# Puzzle_OLED128x32-I2C.net
KiCad netlist of a schematic drawn in EAGLE
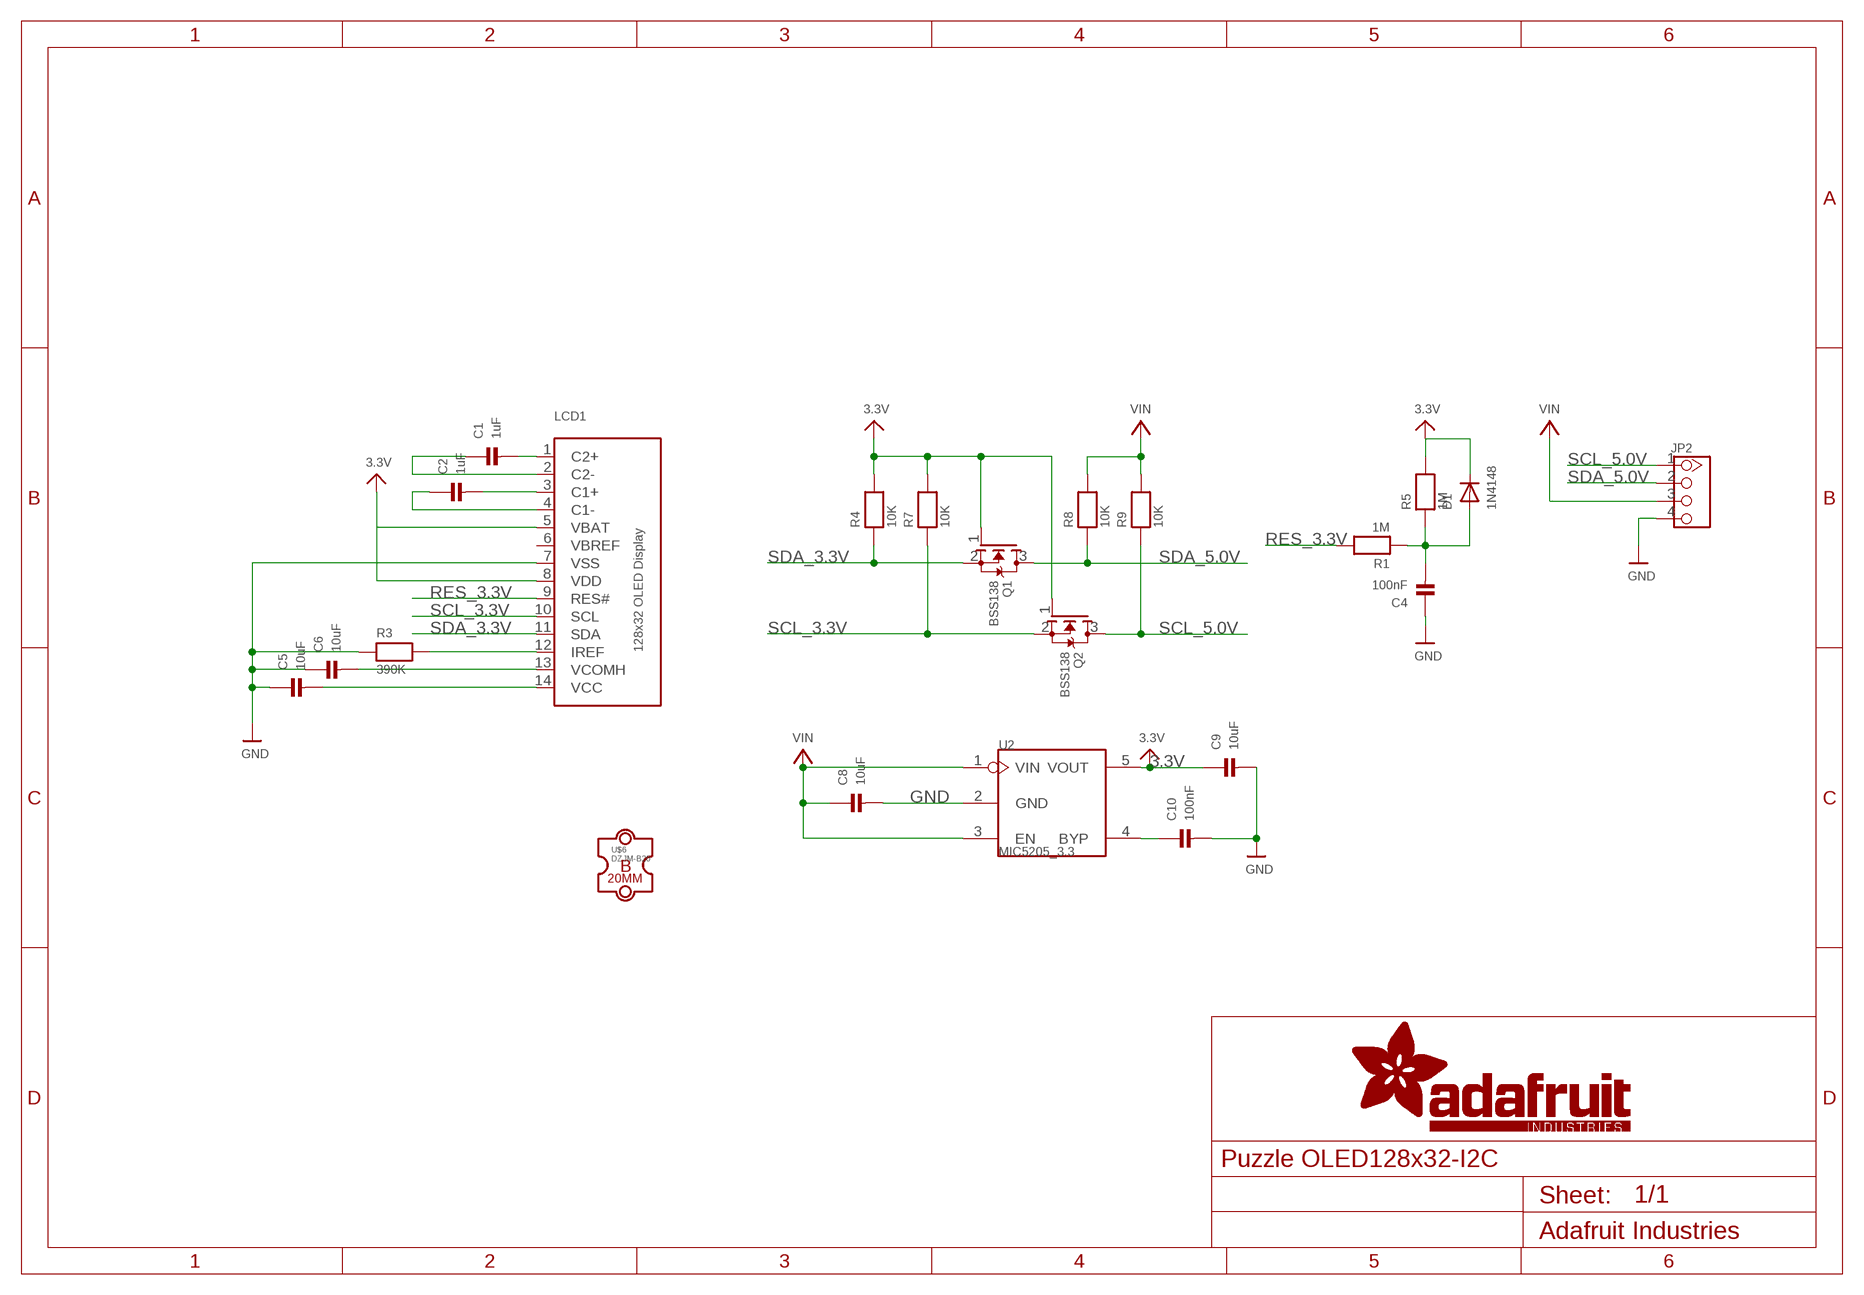
[diagram p0: schematic, sheet 1]

(export (version "E")
  (design (tool "Eeschema 10.0.6"))
  (components
    (comp (ref "C1")
      (value "1uF")
      (footprint "eagle-import:0603")
      (libsource (lib "eagle-import") (part "CAP_CERAMIC0603"))
    )
    (comp (ref "C2")
      (value "1uF")
      (footprint "eagle-import:0603")
      (libsource (lib "eagle-import") (part "CAP_CERAMIC0603"))
    )
    (comp (ref "C4")
      (value "100nF")
      (footprint "eagle-import:0603")
      (libsource (lib "eagle-import") (part "CAP_CERAMIC0603"))
    )
    (comp (ref "C5")
      (value "10uF")
      (footprint "eagle-import:0805")
      (libsource (lib "eagle-import") (part "CAP_CERAMIC0805"))
    )
    (comp (ref "C6")
      (value "10uF")
      (footprint "eagle-import:0805")
      (libsource (lib "eagle-import") (part "CAP_CERAMIC0805"))
    )
    (comp (ref "C8")
      (value "10uF")
      (footprint "eagle-import:0805")
      (libsource (lib "eagle-import") (part "CAP_CERAMIC0805"))
    )
    (comp (ref "C9")
      (value "10uF")
      (footprint "eagle-import:0805")
      (libsource (lib "eagle-import") (part "CAP_CERAMIC0805"))
    )
    (comp (ref "C10")
      (value "100nF")
      (footprint "eagle-import:0603")
      (libsource (lib "eagle-import") (part "CAP_CERAMIC0603"))
    )
    (comp (ref "D1")
      (value "1N4148")
      (footprint "eagle-import:SOD-323F")
      (libsource (lib "eagle-import") (part "DIODESOD-323F"))
    )
    (comp (ref "JP2")
      (value "M048")
      (footprint "eagle-import:4P-SMD-2.0-90D")
      (libsource (lib "eagle-import") (part "M048"))
    )
    (comp (ref "LCD1")
      (value "DISP_OLED_UG-2832HSWEG02")
      (footprint "eagle-import:UG-2832HSWEG02_WRAPUNDER")
      (libsource (lib "eagle-import") (part "DISP_OLED_UG-2832HSWEG02"))
    )
    (comp (ref "Q1")
      (value "BSS138")
      (footprint "eagle-import:SOT23-WIDE")
      (libsource (lib "eagle-import") (part "MOSFET-NWIDE"))
    )
    (comp (ref "Q2")
      (value "BSS138")
      (footprint "eagle-import:SOT23-WIDE")
      (libsource (lib "eagle-import") (part "MOSFET-NWIDE"))
    )
    (comp (ref "R1")
      (value "1M")
      (footprint "eagle-import:0603")
      (libsource (lib "eagle-import") (part "RESISTOR0603"))
    )
    (comp (ref "R3")
      (value "390K")
      (footprint "eagle-import:0603")
      (libsource (lib "eagle-import") (part "RESISTOR0603"))
    )
    (comp (ref "R4")
      (value "10K")
      (footprint "eagle-import:0805")
      (libsource (lib "eagle-import") (part "RESISTOR0805"))
    )
    (comp (ref "R5")
      (value "1M")
      (footprint "eagle-import:0805")
      (libsource (lib "eagle-import") (part "RESISTOR0805"))
    )
    (comp (ref "R7")
      (value "10K")
      (footprint "eagle-import:0805")
      (libsource (lib "eagle-import") (part "RESISTOR0805"))
    )
    (comp (ref "R8")
      (value "10K")
      (footprint "eagle-import:0805")
      (libsource (lib "eagle-import") (part "RESISTOR0805"))
    )
    (comp (ref "R9")
      (value "10K")
      (footprint "eagle-import:0805")
      (libsource (lib "eagle-import") (part "RESISTOR0805"))
    )
    (comp (ref "U$6")
      (value "DZJM-B20")
      (footprint "eagle-import:DZJM-B20-2P-B")
      (libsource (lib "eagle-import") (part "DZJM-B20"))
    )
    (comp (ref "U2")
      (value "MIC5205_3.3")
      (footprint "eagle-import:SOT23-5")
      (libsource (lib "eagle-import") (part "MIC5025_X.X"))
    )
  )
  (nets
    (net (code "1") (name "/RES_3.3V") (class "Default")
      (node (ref "LCD1") (pin "9") (pinfunction "RES#_9") (pintype "bidirectional"))
      (node (ref "R1") (pin "2") (pinfunction "2_2") (pintype "passive"))
    )
    (net (code "2") (name "/SCL_3.3V") (class "Default")
      (node (ref "LCD1") (pin "10") (pinfunction "SCL_10") (pintype "bidirectional"))
      (node (ref "Q2") (pin "2") (pinfunction "S_2") (pintype "bidirectional"))
      (node (ref "R7") (pin "1") (pinfunction "1_1") (pintype "passive"))
    )
    (net (code "3") (name "/SCL_5.0V") (class "Default")
      (node (ref "JP2") (pin "1") (pinfunction "P$1_1") (pintype "bidirectional"))
      (node (ref "Q2") (pin "3") (pinfunction "D_3") (pintype "bidirectional"))
      (node (ref "R9") (pin "1") (pinfunction "1_1") (pintype "passive"))
    )
    (net (code "4") (name "/SDA_3.3V") (class "Default")
      (node (ref "LCD1") (pin "11") (pinfunction "SDA_11") (pintype "bidirectional"))
      (node (ref "Q1") (pin "2") (pinfunction "S_2") (pintype "bidirectional"))
      (node (ref "R4") (pin "1") (pinfunction "1_1") (pintype "passive"))
    )
    (net (code "5") (name "/SDA_5.0V") (class "Default")
      (node (ref "JP2") (pin "2") (pinfunction "P$2_2") (pintype "bidirectional"))
      (node (ref "Q1") (pin "3") (pinfunction "D_3") (pintype "bidirectional"))
      (node (ref "R8") (pin "1") (pinfunction "1_1") (pintype "passive"))
    )
    (net (code "6") (name "/VBREF") (class "Default")
      (node (ref "LCD1") (pin "6") (pinfunction "VBREF_6") (pintype "power_in"))
    )
    (net (code "7") (name "3.3V") (class "Default")
      (node (ref "C9") (pin "1") (pinfunction "P$1_1") (pintype "passive"))
      (node (ref "D1") (pin "C") (pinfunction "C_C") (pintype "passive"))
      (node (ref "LCD1") (pin "5") (pinfunction "VBAT_5") (pintype "power_in"))
      (node (ref "LCD1") (pin "8") (pinfunction "VDD_8") (pintype "power_in"))
      (node (ref "Q1") (pin "1") (pinfunction "G_1") (pintype "bidirectional"))
      (node (ref "Q2") (pin "1") (pinfunction "G_1") (pintype "bidirectional"))
      (node (ref "R4") (pin "2") (pinfunction "2_2") (pintype "passive"))
      (node (ref "R5") (pin "2") (pinfunction "2_2") (pintype "passive"))
      (node (ref "R7") (pin "2") (pinfunction "2_2") (pintype "passive"))
      (node (ref "U2") (pin "5") (pinfunction "VOUT_5") (pintype "bidirectional"))
    )
    (net (code "8") (name "GND") (class "Default")
      (node (ref "C10") (pin "2") (pinfunction "P$2_2") (pintype "passive"))
      (node (ref "C4") (pin "1") (pinfunction "P$1_1") (pintype "passive"))
      (node (ref "C5") (pin "1") (pinfunction "P$1_1") (pintype "passive"))
      (node (ref "C6") (pin "1") (pinfunction "P$1_1") (pintype "passive"))
      (node (ref "C8") (pin "2") (pinfunction "P$2_2") (pintype "passive"))
      (node (ref "C9") (pin "2") (pinfunction "P$2_2") (pintype "passive"))
      (node (ref "JP2") (pin "4") (pinfunction "P$4_4") (pintype "bidirectional"))
      (node (ref "LCD1") (pin "7") (pinfunction "VSS_7") (pintype "power_in"))
      (node (ref "R3") (pin "1") (pinfunction "1_1") (pintype "passive"))
      (node (ref "U2") (pin "2") (pinfunction "GND_2") (pintype "bidirectional"))
    )
    (net (code "9") (name "Net-(C1-P$1)") (class "Default")
      (node (ref "C1") (pin "1") (pinfunction "P$1_1") (pintype "passive"))
      (node (ref "LCD1") (pin "2") (pinfunction "C2-_2") (pintype "bidirectional"))
    )
    (net (code "10") (name "Net-(C1-P$2)") (class "Default")
      (node (ref "C1") (pin "2") (pinfunction "P$2_2") (pintype "passive"))
      (node (ref "LCD1") (pin "1") (pinfunction "C2+_1") (pintype "bidirectional"))
    )
    (net (code "11") (name "Net-(C2-P$1)") (class "Default")
      (node (ref "C2") (pin "1") (pinfunction "P$1_1") (pintype "passive"))
      (node (ref "LCD1") (pin "4") (pinfunction "C1-_4") (pintype "bidirectional"))
    )
    (net (code "12") (name "Net-(C2-P$2)") (class "Default")
      (node (ref "C2") (pin "2") (pinfunction "P$2_2") (pintype "passive"))
      (node (ref "LCD1") (pin "3") (pinfunction "C1+_3") (pintype "bidirectional"))
    )
    (net (code "13") (name "Net-(C4-P$2)") (class "Default")
      (node (ref "C4") (pin "2") (pinfunction "P$2_2") (pintype "passive"))
      (node (ref "D1") (pin "A") (pinfunction "A_A") (pintype "passive"))
      (node (ref "R1") (pin "1") (pinfunction "1_1") (pintype "passive"))
      (node (ref "R5") (pin "1") (pinfunction "1_1") (pintype "passive"))
    )
    (net (code "14") (name "Net-(C5-P$2)") (class "Default")
      (node (ref "C5") (pin "2") (pinfunction "P$2_2") (pintype "passive"))
      (node (ref "LCD1") (pin "14") (pinfunction "VCC_14") (pintype "power_in"))
    )
    (net (code "15") (name "Net-(C6-P$2)") (class "Default")
      (node (ref "C6") (pin "2") (pinfunction "P$2_2") (pintype "passive"))
      (node (ref "LCD1") (pin "13") (pinfunction "VCOMH_13") (pintype "power_in"))
    )
    (net (code "16") (name "Net-(C10-P$1)") (class "Default")
      (node (ref "C10") (pin "1") (pinfunction "P$1_1") (pintype "passive"))
      (node (ref "U2") (pin "4") (pinfunction "BYP_4") (pintype "bidirectional"))
    )
    (net (code "17") (name "Net-(LCD1-IREF)") (class "Default")
      (node (ref "LCD1") (pin "12") (pinfunction "IREF_12") (pintype "bidirectional"))
      (node (ref "R3") (pin "2") (pinfunction "2_2") (pintype "passive"))
    )
    (net (code "18") (name "VIN") (class "Default")
      (node (ref "C8") (pin "1") (pinfunction "P$1_1") (pintype "passive"))
      (node (ref "JP2") (pin "3") (pinfunction "P$3_3") (pintype "bidirectional"))
      (node (ref "R8") (pin "2") (pinfunction "2_2") (pintype "passive"))
      (node (ref "R9") (pin "2") (pinfunction "2_2") (pintype "passive"))
      (node (ref "U2") (pin "1") (pinfunction "VIN_1") (pintype "bidirectional"))
      (node (ref "U2") (pin "3") (pinfunction "EN_3") (pintype "bidirectional"))
    )
  )
)
